# MCU_adacus_sch.net
KiCad netlist of a schematic drawn in Altium Designer
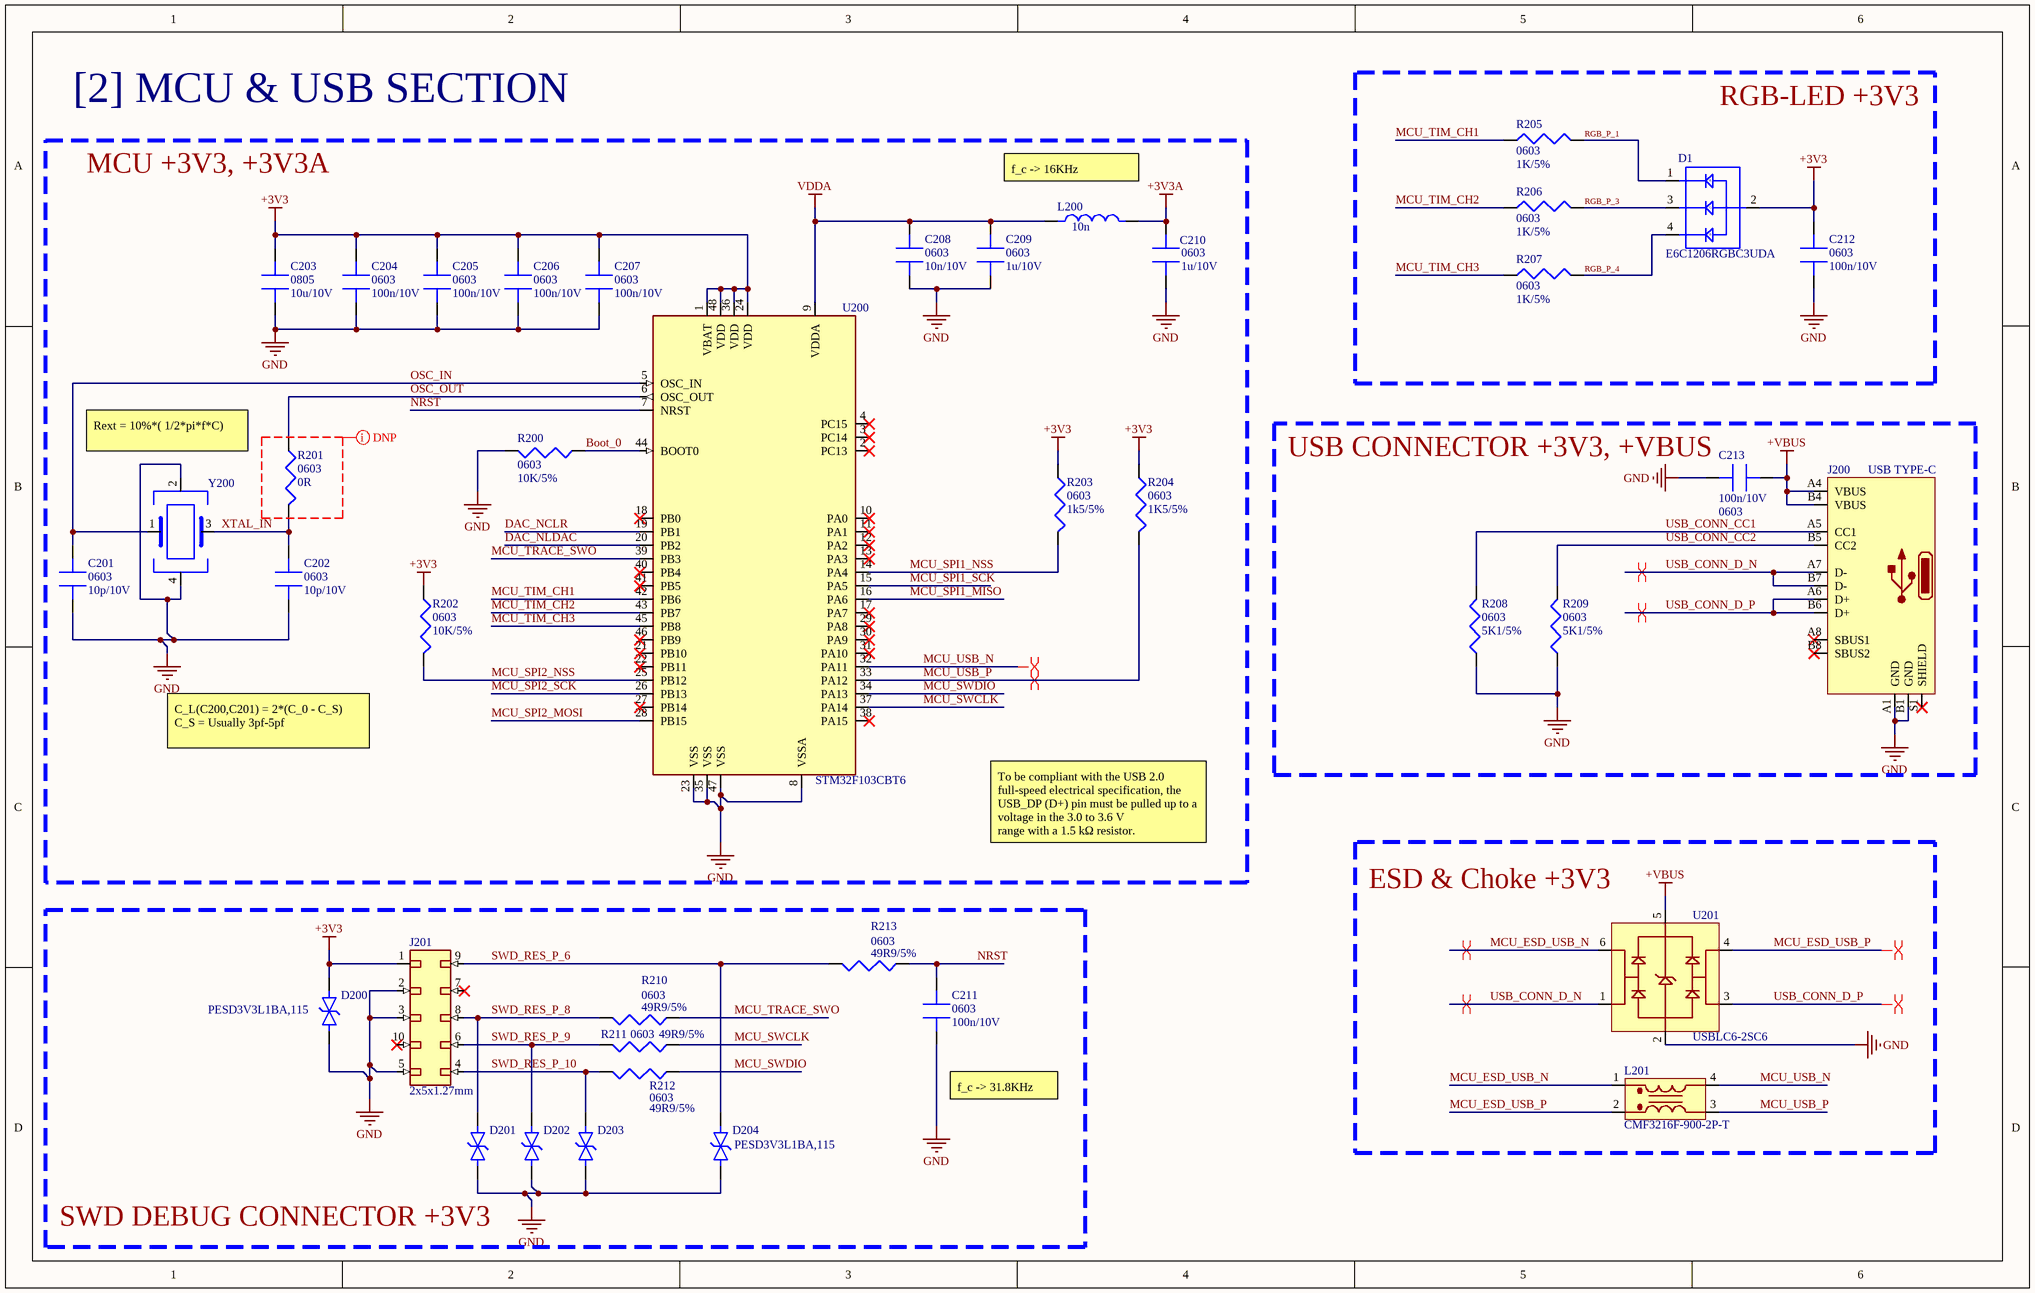
[diagram p0: MCU_adacus_sch.SchDoc]

(export (version "E")
  (design (tool "Eeschema 10.0.6"))
  (components
    (comp (ref "C201")
      (value "10p/10V")
      (footprint "[0603] CAPC1608X10M [A-LD]")
      (description "Standard Capacitor")
      (fields (field (name "PACKAGE") "0603") (field (name "Comment") "Capacitor"))
      (libsource (lib "adacus_schlib") (part "Capacitor"))
    )
    (comp (ref "C202")
      (value "10p/10V")
      (footprint "[0603] CAPC1608X10M [A-LD]")
      (description "Standard Capacitor")
      (fields (field (name "PACKAGE") "0603") (field (name "Comment") "Capacitor"))
      (libsource (lib "adacus_schlib") (part "Capacitor"))
    )
    (comp (ref "C203")
      (value "10u/10V")
      (footprint "[0805] CAPC2012X09M [A - LD]")
      (description "Standard Capacitor")
      (fields (field (name "PACKAGE") "0805") (field (name "Comment") "Capacitor"))
      (libsource (lib "adacus_schlib") (part "Capacitor"))
    )
    (comp (ref "C204")
      (value "100n/10V")
      (footprint "[0603] CAPC1608X10M [A-LD]")
      (description "Standard Capacitor")
      (fields (field (name "PACKAGE") "0603") (field (name "Comment") "Capacitor"))
      (libsource (lib "adacus_schlib") (part "Capacitor"))
    )
    (comp (ref "C205")
      (value "100n/10V")
      (footprint "[0603] CAPC1608X10M [A-LD]")
      (description "Standard Capacitor")
      (fields (field (name "PACKAGE") "0603") (field (name "Comment") "Capacitor"))
      (libsource (lib "adacus_schlib") (part "Capacitor"))
    )
    (comp (ref "C206")
      (value "100n/10V")
      (footprint "[0603] CAPC1608X10M [A-LD]")
      (description "Standard Capacitor")
      (fields (field (name "PACKAGE") "0603") (field (name "Comment") "Capacitor"))
      (libsource (lib "adacus_schlib") (part "Capacitor"))
    )
    (comp (ref "C207")
      (value "100n/10V")
      (footprint "[0603] CAPC1608X10M [A-LD]")
      (description "Standard Capacitor")
      (fields (field (name "PACKAGE") "0603") (field (name "Comment") "Capacitor"))
      (libsource (lib "adacus_schlib") (part "Capacitor"))
    )
    (comp (ref "C208")
      (value "10n/10V")
      (footprint "[0603] CAPC1608X10M [A-LD]")
      (description "Standard Capacitor")
      (fields (field (name "PACKAGE") "0603") (field (name "Comment") "Capacitor"))
      (libsource (lib "adacus_schlib") (part "Capacitor"))
    )
    (comp (ref "C209")
      (value "1u/10V")
      (footprint "[0805] CAPC2012X09M [A - LD]")
      (description "Standard Capacitor")
      (fields (field (name "PACKAGE") "0603") (field (name "Comment") "Capacitor"))
      (libsource (lib "adacus_schlib") (part "Capacitor"))
    )
    (comp (ref "C210")
      (value "1u/10V")
      (footprint "[0805] CAPC2012X09M [A - LD]")
      (description "Standard Capacitor")
      (fields (field (name "PACKAGE") "0603") (field (name "Comment") "Capacitor"))
      (libsource (lib "adacus_schlib") (part "Capacitor"))
    )
    (comp (ref "C211")
      (value "100n/10V")
      (footprint "[0603] CAPC1608X10M [A-LD]")
      (description "Standard Capacitor")
      (fields (field (name "PACKAGE") "0603") (field (name "Comment") "Capacitor"))
      (libsource (lib "adacus_schlib") (part "Capacitor"))
    )
    (comp (ref "C212")
      (value "100n/10V")
      (footprint "[0603] CAPC1608X10M [A-LD]")
      (description "Standard Capacitor")
      (fields (field (name "PACKAGE") "0603") (field (name "Comment") "Capacitor"))
      (libsource (lib "adacus_schlib") (part "Capacitor"))
    )
    (comp (ref "C213")
      (value "100n/10V")
      (footprint "[0603] CAPC1608X10M [A-LD]")
      (description "Standard Capacitor")
      (fields (field (name "PACKAGE") "0603") (field (name "Comment") "Capacitor"))
      (libsource (lib "adacus_schlib") (part "Capacitor"))
    )
    (comp (ref "D1")
      (value "E6C1206RGBC3UDA")
      (footprint "E6C1206RGBC3UDA")
      (description "RGB 1206 Light Emitting Diodes (LED) ROHS")
      (libsource (lib "adacus_schlib") (part "LED_RGB"))
    )
    (comp (ref "D200")
      (value "PESD3V3L1BA,115")
      (footprint "SODFL250X110-2M")
      (description "ESD Suppressors / TVS Diodes PESD3V3L1BA/SOD323/SOD2")
      (libsource (lib "adacus_schlib") (part "PESD3V3L1BA,115"))
    )
    (comp (ref "D201")
      (value "PESD3V3L1BA,115")
      (footprint "SODFL250X110-2M")
      (description "ESD Suppressors / TVS Diodes PESD3V3L1BA/SOD323/SOD2")
      (libsource (lib "adacus_schlib") (part "PESD3V3L1BA,115"))
    )
    (comp (ref "D202")
      (value "PESD3V3L1BA,115")
      (footprint "SODFL250X110-2M")
      (description "ESD Suppressors / TVS Diodes PESD3V3L1BA/SOD323/SOD2")
      (libsource (lib "adacus_schlib") (part "PESD3V3L1BA,115"))
    )
    (comp (ref "D203")
      (value "PESD3V3L1BA,115")
      (footprint "SODFL250X110-2M")
      (description "ESD Suppressors / TVS Diodes PESD3V3L1BA/SOD323/SOD2")
      (libsource (lib "adacus_schlib") (part "PESD3V3L1BA,115"))
    )
    (comp (ref "D204")
      (value "PESD3V3L1BA,115")
      (footprint "SODFL250X110-2M")
      (description "ESD Suppressors / TVS Diodes PESD3V3L1BA/SOD323/SOD2")
      (libsource (lib "adacus_schlib") (part "PESD3V3L1BA,115"))
    )
    (comp (ref "J200")
      (value "USB TYPE-C")
      (footprint "HRO_TYPE-C-31-M-12")
      (libsource (lib "adacus_schlib") (part "USB TYPE-C"))
    )
    (comp (ref "J201")
      (value "2x5x1.27mm")
      (footprint "2X10_BOXHEADER")
      (description "SWD Connector 2x5x1.27mm pin count")
      (libsource (lib "adacus_schlib") (part "SWD Connector"))
    )
    (comp (ref "L200")
      (value "10n")
      (footprint "PM0603-10NJ")
      (description "Standard Inductor")
      (fields (field (name "Comment") "Inductor"))
      (libsource (lib "adacus_schlib") (part "Inductor"))
    )
    (comp (ref "L201")
      (value "CMF3216F-900-2P-T")
      (footprint "CMF3216F-900-2P-T")
      (description "90Ω@100MHz 0.3Ω 2 1206 Common Mode Filters ROHS")
      (libsource (lib "adacus_schlib") (part "CMF3216F-900-2P-T"))
    )
    (comp (ref "R200")
      (value "10K/5%")
      (footprint "[0603] RESC1608X06M [A-LD]")
      (description "Standard Resistor")
      (fields (field (name "PACKAGE") "0603") (field (name "Comment") "Resistor"))
      (libsource (lib "adacus_schlib") (part "Resistor"))
    )
    (comp (ref "R201")
      (value "0R")
      (footprint "[0603] RESC1608X06M [A-LD]")
      (description "Standard Resistor")
      (fields (field (name "PACKAGE") "0603") (field (name "Comment") "Resistor"))
      (libsource (lib "adacus_schlib") (part "Resistor"))
    )
    (comp (ref "R202")
      (value "10K/5%")
      (footprint "[0603] RESC1608X06M [A-LD]")
      (description "Standard Resistor")
      (fields (field (name "PACKAGE") "0603") (field (name "Comment") "Resistor"))
      (libsource (lib "adacus_schlib") (part "Resistor"))
    )
    (comp (ref "R203")
      (value "1k5/5%")
      (footprint "[0603] RESC1608X06M [A-LD]")
      (description "Standard Resistor")
      (fields (field (name "PACKAGE") "0603") (field (name "Comment") "Resistor"))
      (libsource (lib "adacus_schlib") (part "Resistor"))
    )
    (comp (ref "R204")
      (value "1K5/5%")
      (footprint "[0603] RESC1608X06M [A-LD]")
      (description "Standard Resistor")
      (fields (field (name "PACKAGE") "0603") (field (name "Comment") "Resistor"))
      (libsource (lib "adacus_schlib") (part "Resistor"))
    )
    (comp (ref "R205")
      (value "1K/5%")
      (footprint "[0603] RESC1608X06M [A-LD]")
      (description "Standard Resistor")
      (fields (field (name "PACKAGE") "0603") (field (name "Comment") "Resistor"))
      (libsource (lib "adacus_schlib") (part "Resistor"))
    )
    (comp (ref "R206")
      (value "1K/5%")
      (footprint "[0603] RESC1608X06M [A-LD]")
      (description "Standard Resistor")
      (fields (field (name "PACKAGE") "0603") (field (name "Comment") "Resistor"))
      (libsource (lib "adacus_schlib") (part "Resistor"))
    )
    (comp (ref "R207")
      (value "1K/5%")
      (footprint "[0603] RESC1608X06M [A-LD]")
      (description "Standard Resistor")
      (fields (field (name "PACKAGE") "0603") (field (name "Comment") "Resistor"))
      (libsource (lib "adacus_schlib") (part "Resistor"))
    )
    (comp (ref "R208")
      (value "5K1/5%")
      (footprint "[0603] RESC1608X06M [A-LD]")
      (description "Standard Resistor")
      (fields (field (name "PACKAGE") "0603") (field (name "Comment") "Resistor"))
      (libsource (lib "adacus_schlib") (part "Resistor"))
    )
    (comp (ref "R209")
      (value "5K1/5%")
      (footprint "[0603] RESC1608X06M [A-LD]")
      (description "Standard Resistor")
      (fields (field (name "PACKAGE") "0603") (field (name "Comment") "Resistor"))
      (libsource (lib "adacus_schlib") (part "Resistor"))
    )
    (comp (ref "R210")
      (value "49R9/5%")
      (footprint "[0603] RESC1608X06M [A-LD]")
      (description "Standard Resistor")
      (fields (field (name "PACKAGE") "0603") (field (name "Comment") "Resistor"))
      (libsource (lib "adacus_schlib") (part "Resistor"))
    )
    (comp (ref "R211")
      (value "49R9/5%")
      (footprint "[0603] RESC1608X06M [A-LD]")
      (description "Standard Resistor")
      (fields (field (name "PACKAGE") "0603") (field (name "Comment") "Resistor"))
      (libsource (lib "adacus_schlib") (part "Resistor"))
    )
    (comp (ref "R212")
      (value "49R9/5%")
      (footprint "[0603] RESC1608X06M [A-LD]")
      (description "Standard Resistor")
      (fields (field (name "PACKAGE") "0603") (field (name "Comment") "Resistor"))
      (libsource (lib "adacus_schlib") (part "Resistor"))
    )
    (comp (ref "R213")
      (value "49R9/5%")
      (footprint "[0603] RESC1608X06M [A-LD]")
      (description "Standard Resistor")
      (fields (field (name "PACKAGE") "0603") (field (name "Comment") "Resistor"))
      (libsource (lib "adacus_schlib") (part "Resistor"))
    )
    (comp (ref "U200")
      (value "STM32F103CBT6")
      (footprint "TSQFP50P900X900X160-48M")
      (description "ARM Microcontrollers - MCU 32BIT Cortex M3 128K MED Performance LN")
      (libsource (lib "adacus_schlib") (part "STM32F103CBT6"))
    )
    (comp (ref "U201")
      (value "USBLC6-2SC6")
      (footprint "SOT95P280X145-6M")
      (description "Very low capacitance ESD protection")
      (libsource (lib "adacus_schlib") (part "USBLC6-2"))
    )
    (comp (ref "Y200")
      (value "ECS-2016MV-160-DN")
      (footprint "ECS-2016MV-160-DN")
      (libsource (lib "adacus_schlib") (part "ECS-2016MV-160-DN"))
    )
  )
  (nets
    (net (code "1") (name "+3V3") (class "Default")
      (node (ref "C203") (pin "2") (pinfunction "2_2") (pintype "passive"))
      (node (ref "C204") (pin "2") (pinfunction "2_2") (pintype "passive"))
      (node (ref "C205") (pin "2") (pinfunction "2_2") (pintype "passive"))
      (node (ref "C206") (pin "2") (pinfunction "2_2") (pintype "passive"))
      (node (ref "C207") (pin "2") (pinfunction "2_2") (pintype "passive"))
      (node (ref "C212") (pin "2") (pinfunction "2_2") (pintype "passive"))
      (node (ref "D1") (pin "2") (pinfunction "2_2") (pintype "passive"))
      (node (ref "D200") (pin "2") (pinfunction "2_2") (pintype "passive"))
      (node (ref "J201") (pin "1") (pinfunction "VCC_1") (pintype "power_in"))
      (node (ref "R202") (pin "2") (pinfunction "2_2") (pintype "passive"))
      (node (ref "R203") (pin "2") (pinfunction "2_2") (pintype "passive"))
      (node (ref "R204") (pin "2") (pinfunction "2_2") (pintype "passive"))
      (node (ref "U200") (pin "1") (pinfunction "VBAT_1") (pintype "power_in"))
      (node (ref "U200") (pin "24") (pinfunction "VDD_24") (pintype "power_in"))
      (node (ref "U200") (pin "36") (pinfunction "VDD_36") (pintype "power_in"))
      (node (ref "U200") (pin "48") (pinfunction "VDD_48") (pintype "power_in"))
    )
    (net (code "2") (name "+3V3A") (class "Default")
      (node (ref "C210") (pin "2") (pinfunction "2_2") (pintype "passive"))
      (node (ref "L200") (pin "1") (pinfunction "1_1") (pintype "passive"))
    )
    (net (code "3") (name "+VBUS") (class "Default")
      (node (ref "C213") (pin "2") (pinfunction "2_2") (pintype "passive"))
      (node (ref "J200") (pin "A4") (pinfunction "VBUS_A4") (pintype "passive"))
      (node (ref "J200") (pin "B4") (pinfunction "VBUS_B4") (pintype "passive"))
      (node (ref "U201") (pin "5") (pinfunction "5_5") (pintype "passive"))
    )
    (net (code "4") (name "/Boot_0") (class "Default")
      (node (ref "R200") (pin "2") (pinfunction "2_2") (pintype "passive"))
      (node (ref "U200") (pin "44") (pinfunction "BOOT0_44") (pintype "input"))
    )
    (net (code "5") (name "/DAC_NCLR") (class "Default")
      (node (ref "U200") (pin "19") (pinfunction "PB1_19") (pintype "bidirectional"))
    )
    (net (code "6") (name "/DAC_NLDAC") (class "Default")
      (node (ref "U200") (pin "20") (pinfunction "PB2_20") (pintype "bidirectional"))
    )
    (net (code "7") (name "/MCU_ESD_USB_N") (class "Default")
      (node (ref "L201") (pin "1") (pinfunction "1_1") (pintype "passive"))
      (node (ref "U201") (pin "6") (pinfunction "6_6") (pintype "passive"))
    )
    (net (code "8") (name "/MCU_ESD_USB_P") (class "Default")
      (node (ref "L201") (pin "2") (pinfunction "2_2") (pintype "passive"))
      (node (ref "U201") (pin "4") (pinfunction "4_4") (pintype "passive"))
    )
    (net (code "9") (name "/MCU_SPI1_MISO") (class "Default")
      (node (ref "U200") (pin "16") (pinfunction "PA6_16") (pintype "bidirectional"))
    )
    (net (code "10") (name "/MCU_SPI1_NSS") (class "Default")
      (node (ref "R203") (pin "1") (pinfunction "1_1") (pintype "passive"))
      (node (ref "U200") (pin "14") (pinfunction "PA4_14") (pintype "bidirectional"))
    )
    (net (code "11") (name "/MCU_SPI1_SCK") (class "Default")
      (node (ref "U200") (pin "15") (pinfunction "PA5_15") (pintype "bidirectional"))
    )
    (net (code "12") (name "/MCU_SPI2_MOSI") (class "Default")
      (node (ref "U200") (pin "28") (pinfunction "PB15_28") (pintype "bidirectional"))
    )
    (net (code "13") (name "/MCU_SPI2_NSS") (class "Default")
      (node (ref "R202") (pin "1") (pinfunction "1_1") (pintype "passive"))
      (node (ref "U200") (pin "25") (pinfunction "PB12_25") (pintype "bidirectional"))
    )
    (net (code "14") (name "/MCU_SPI2_SCK") (class "Default")
      (node (ref "U200") (pin "26") (pinfunction "PB13_26") (pintype "bidirectional"))
    )
    (net (code "15") (name "/MCU_SWCLK") (class "Default")
      (node (ref "R211") (pin "2") (pinfunction "2_2") (pintype "passive"))
      (node (ref "U200") (pin "37") (pinfunction "PA14_37") (pintype "bidirectional"))
    )
    (net (code "16") (name "/MCU_SWDIO") (class "Default")
      (node (ref "R212") (pin "2") (pinfunction "2_2") (pintype "passive"))
      (node (ref "U200") (pin "34") (pinfunction "PA13_34") (pintype "bidirectional"))
    )
    (net (code "17") (name "/MCU_TIM_CH1") (class "Default")
      (node (ref "R205") (pin "2") (pinfunction "2_2") (pintype "passive"))
      (node (ref "U200") (pin "42") (pinfunction "PB6_42") (pintype "bidirectional"))
    )
    (net (code "18") (name "/MCU_TIM_CH2") (class "Default")
      (node (ref "R206") (pin "2") (pinfunction "2_2") (pintype "passive"))
      (node (ref "U200") (pin "43") (pinfunction "PB7_43") (pintype "bidirectional"))
    )
    (net (code "19") (name "/MCU_TIM_CH3") (class "Default")
      (node (ref "R207") (pin "2") (pinfunction "2_2") (pintype "passive"))
      (node (ref "U200") (pin "45") (pinfunction "PB8_45") (pintype "bidirectional"))
    )
    (net (code "20") (name "/MCU_TRACE_SWO") (class "Default")
      (node (ref "R210") (pin "2") (pinfunction "2_2") (pintype "passive"))
      (node (ref "U200") (pin "39") (pinfunction "PB3_39") (pintype "bidirectional"))
    )
    (net (code "21") (name "/MCU_USB_N") (class "Default")
      (node (ref "L201") (pin "4") (pinfunction "4_4") (pintype "passive"))
      (node (ref "U200") (pin "32") (pinfunction "PA11_32") (pintype "bidirectional"))
    )
    (net (code "22") (name "/MCU_USB_P") (class "Default")
      (node (ref "L201") (pin "3") (pinfunction "3_3") (pintype "passive"))
      (node (ref "R204") (pin "1") (pinfunction "1_1") (pintype "passive"))
      (node (ref "U200") (pin "33") (pinfunction "PA12_33") (pintype "bidirectional"))
    )
    (net (code "23") (name "/NRST") (class "Default")
      (node (ref "C211") (pin "2") (pinfunction "2_2") (pintype "passive"))
      (node (ref "R213") (pin "2") (pinfunction "2_2") (pintype "passive"))
      (node (ref "U200") (pin "7") (pinfunction "NRST_7") (pintype "bidirectional"))
    )
    (net (code "24") (name "/OSC_IN") (class "Default")
      (node (ref "C201") (pin "2") (pinfunction "2_2") (pintype "passive"))
      (node (ref "U200") (pin "5") (pinfunction "OSC_IN_5") (pintype "input"))
      (node (ref "Y200") (pin "1") (pinfunction "1_1") (pintype "passive"))
    )
    (net (code "25") (name "/OSC_OUT") (class "Default")
      (node (ref "R201") (pin "2") (pinfunction "2_2") (pintype "passive"))
      (node (ref "U200") (pin "6") (pinfunction "OSC_OUT_6") (pintype "output"))
    )
    (net (code "26") (name "/RGB_P_1") (class "Default")
      (node (ref "D1") (pin "1") (pinfunction "1_1") (pintype "passive"))
      (node (ref "R205") (pin "1") (pinfunction "1_1") (pintype "passive"))
    )
    (net (code "27") (name "/RGB_P_3") (class "Default")
      (node (ref "D1") (pin "3") (pinfunction "3_3") (pintype "passive"))
      (node (ref "R206") (pin "1") (pinfunction "1_1") (pintype "passive"))
    )
    (net (code "28") (name "/RGB_P_4") (class "Default")
      (node (ref "D1") (pin "4") (pinfunction "4_4") (pintype "passive"))
      (node (ref "R207") (pin "1") (pinfunction "1_1") (pintype "passive"))
    )
    (net (code "29") (name "/SWD_RES_P_6") (class "Default")
      (node (ref "D204") (pin "2") (pinfunction "2_2") (pintype "passive"))
      (node (ref "J201") (pin "9") (pinfunction "TDO_9") (pintype "input"))
      (node (ref "R213") (pin "1") (pinfunction "1_1") (pintype "passive"))
    )
    (net (code "30") (name "/SWD_RES_P_8") (class "Default")
      (node (ref "D201") (pin "2") (pinfunction "2_2") (pintype "passive"))
      (node (ref "J201") (pin "8") (pinfunction "TDI_8") (pintype "input"))
      (node (ref "R210") (pin "1") (pinfunction "1_1") (pintype "passive"))
    )
    (net (code "31") (name "/SWD_RES_P_9") (class "Default")
      (node (ref "D202") (pin "2") (pinfunction "2_2") (pintype "passive"))
      (node (ref "J201") (pin "6") (pinfunction "TCK_6") (pintype "input"))
      (node (ref "R211") (pin "1") (pinfunction "1_1") (pintype "passive"))
    )
    (net (code "32") (name "/SWD_RES_P_10") (class "Default")
      (node (ref "D203") (pin "2") (pinfunction "2_2") (pintype "passive"))
      (node (ref "J201") (pin "4") (pinfunction "nRESET_4") (pintype "input"))
      (node (ref "R212") (pin "1") (pinfunction "1_1") (pintype "passive"))
    )
    (net (code "33") (name "/USB_CONN_CC1") (class "Default")
      (node (ref "J200") (pin "A5") (pinfunction "CC1_A5") (pintype "passive"))
      (node (ref "R208") (pin "1") (pinfunction "1_1") (pintype "passive"))
    )
    (net (code "34") (name "/USB_CONN_CC2") (class "Default")
      (node (ref "J200") (pin "B5") (pinfunction "CC2_B5") (pintype "passive"))
      (node (ref "R209") (pin "1") (pinfunction "1_1") (pintype "passive"))
    )
    (net (code "35") (name "/USB_CONN_D_N") (class "Default")
      (node (ref "J200") (pin "A7") (pinfunction "D-_A7") (pintype "passive"))
      (node (ref "J200") (pin "B7") (pinfunction "D-_B7") (pintype "passive"))
      (node (ref "U201") (pin "1") (pinfunction "1_1") (pintype "passive"))
    )
    (net (code "36") (name "/USB_CONN_D_P") (class "Default")
      (node (ref "J200") (pin "A6") (pinfunction "D+_A6") (pintype "passive"))
      (node (ref "J200") (pin "B6") (pinfunction "D+_B6") (pintype "passive"))
      (node (ref "U201") (pin "3") (pinfunction "3_3") (pintype "passive"))
    )
    (net (code "37") (name "/XTAL_IN") (class "Default")
      (node (ref "C202") (pin "2") (pinfunction "2_2") (pintype "passive"))
      (node (ref "R201") (pin "1") (pinfunction "1_1") (pintype "passive"))
      (node (ref "Y200") (pin "3") (pinfunction "3_3") (pintype "passive"))
    )
    (net (code "38") (name "GND") (class "Default")
      (node (ref "C201") (pin "1") (pinfunction "1_1") (pintype "passive"))
      (node (ref "C202") (pin "1") (pinfunction "1_1") (pintype "passive"))
      (node (ref "C203") (pin "1") (pinfunction "1_1") (pintype "passive"))
      (node (ref "C204") (pin "1") (pinfunction "1_1") (pintype "passive"))
      (node (ref "C205") (pin "1") (pinfunction "1_1") (pintype "passive"))
      (node (ref "C206") (pin "1") (pinfunction "1_1") (pintype "passive"))
      (node (ref "C207") (pin "1") (pinfunction "1_1") (pintype "passive"))
      (node (ref "C208") (pin "1") (pinfunction "1_1") (pintype "passive"))
      (node (ref "C209") (pin "1") (pinfunction "1_1") (pintype "passive"))
      (node (ref "C210") (pin "1") (pinfunction "1_1") (pintype "passive"))
      (node (ref "C211") (pin "1") (pinfunction "1_1") (pintype "passive"))
      (node (ref "C212") (pin "1") (pinfunction "1_1") (pintype "passive"))
      (node (ref "C213") (pin "1") (pinfunction "1_1") (pintype "passive"))
      (node (ref "D200") (pin "1") (pinfunction "1_1") (pintype "passive"))
      (node (ref "D201") (pin "1") (pinfunction "1_1") (pintype "passive"))
      (node (ref "D202") (pin "1") (pinfunction "1_1") (pintype "passive"))
      (node (ref "D203") (pin "1") (pinfunction "1_1") (pintype "passive"))
      (node (ref "D204") (pin "1") (pinfunction "1_1") (pintype "passive"))
      (node (ref "J200") (pin "A1") (pinfunction "GND_A1") (pintype "passive"))
      (node (ref "J200") (pin "B1") (pinfunction "GND_B1") (pintype "passive"))
      (node (ref "J201") (pin "2") (pinfunction "TMS_2") (pintype "input"))
      (node (ref "J201") (pin "3") (pinfunction "GND_3") (pintype "input"))
      (node (ref "J201") (pin "5") (pinfunction "GND_5") (pintype "input"))
      (node (ref "R200") (pin "1") (pinfunction "1_1") (pintype "passive"))
      (node (ref "R208") (pin "2") (pinfunction "2_2") (pintype "passive"))
      (node (ref "R209") (pin "2") (pinfunction "2_2") (pintype "passive"))
      (node (ref "U200") (pin "23") (pinfunction "VSS_23") (pintype "power_in"))
      (node (ref "U200") (pin "35") (pinfunction "VSS_35") (pintype "power_in"))
      (node (ref "U200") (pin "47") (pinfunction "VSS_47") (pintype "power_in"))
      (node (ref "U200") (pin "8") (pinfunction "VSSA_8") (pintype "power_in"))
      (node (ref "U201") (pin "2") (pinfunction "2_2") (pintype "passive"))
      (node (ref "Y200") (pin "2") (pinfunction "3_2") (pintype "passive"))
      (node (ref "Y200") (pin "4") (pinfunction "4_4") (pintype "passive"))
    )
    (net (code "39") (name "VDDA") (class "Default")
      (node (ref "C208") (pin "2") (pinfunction "2_2") (pintype "passive"))
      (node (ref "C209") (pin "2") (pinfunction "2_2") (pintype "passive"))
      (node (ref "L200") (pin "2") (pinfunction "2_2") (pintype "passive"))
      (node (ref "U200") (pin "9") (pinfunction "VDDA_9") (pintype "power_in"))
    )
    (net (code "40") (name "unconnected-(J200-SBUS1-PadA8)") (class "Default")
      (node (ref "J200") (pin "A8") (pinfunction "SBUS1_A8") (pintype "passive+no_connect"))
    )
    (net (code "41") (name "unconnected-(J200-SBUS2-PadB8)") (class "Default")
      (node (ref "J200") (pin "B8") (pinfunction "SBUS2_B8") (pintype "passive+no_connect"))
    )
    (net (code "42") (name "unconnected-(J200-SHIELD-PadS1)") (class "Default")
      (node (ref "J200") (pin "S1") (pinfunction "SHIELD_S1") (pintype "passive+no_connect"))
    )
    (net (code "43") (name "unconnected-(J201-GND-Pad10)") (class "Default")
      (node (ref "J201") (pin "10") (pinfunction "GND_10") (pintype "input+no_connect"))
    )
    (net (code "44") (name "unconnected-(J201-KEY-Pad7)") (class "Default")
      (node (ref "J201") (pin "7") (pinfunction "KEY_7") (pintype "input+no_connect"))
    )
    (net (code "45") (name "unconnected-(U200-PA0-Pad10)") (class "Default")
      (node (ref "U200") (pin "10") (pinfunction "PA0_10") (pintype "bidirectional+no_connect"))
    )
    (net (code "46") (name "unconnected-(U200-PA1-Pad11)") (class "Default")
      (node (ref "U200") (pin "11") (pinfunction "PA1_11") (pintype "bidirectional+no_connect"))
    )
    (net (code "47") (name "unconnected-(U200-PA2-Pad12)") (class "Default")
      (node (ref "U200") (pin "12") (pinfunction "PA2_12") (pintype "bidirectional+no_connect"))
    )
    (net (code "48") (name "unconnected-(U200-PA3-Pad13)") (class "Default")
      (node (ref "U200") (pin "13") (pinfunction "PA3_13") (pintype "bidirectional+no_connect"))
    )
    (net (code "49") (name "unconnected-(U200-PA7-Pad17)") (class "Default")
      (node (ref "U200") (pin "17") (pinfunction "PA7_17") (pintype "bidirectional+no_connect"))
    )
    (net (code "50") (name "unconnected-(U200-PA8-Pad29)") (class "Default")
      (node (ref "U200") (pin "29") (pinfunction "PA8_29") (pintype "bidirectional+no_connect"))
    )
    (net (code "51") (name "unconnected-(U200-PA9-Pad30)") (class "Default")
      (node (ref "U200") (pin "30") (pinfunction "PA9_30") (pintype "bidirectional+no_connect"))
    )
    (net (code "52") (name "unconnected-(U200-PA10-Pad31)") (class "Default")
      (node (ref "U200") (pin "31") (pinfunction "PA10_31") (pintype "bidirectional+no_connect"))
    )
    (net (code "53") (name "unconnected-(U200-PA15-Pad38)") (class "Default")
      (node (ref "U200") (pin "38") (pinfunction "PA15_38") (pintype "bidirectional+no_connect"))
    )
    (net (code "54") (name "unconnected-(U200-PB0-Pad18)") (class "Default")
      (node (ref "U200") (pin "18") (pinfunction "PB0_18") (pintype "bidirectional+no_connect"))
    )
    (net (code "55") (name "unconnected-(U200-PB4-Pad40)") (class "Default")
      (node (ref "U200") (pin "40") (pinfunction "PB4_40") (pintype "bidirectional+no_connect"))
    )
    (net (code "56") (name "unconnected-(U200-PB5-Pad41)") (class "Default")
      (node (ref "U200") (pin "41") (pinfunction "PB5_41") (pintype "bidirectional+no_connect"))
    )
    (net (code "57") (name "unconnected-(U200-PB9-Pad46)") (class "Default")
      (node (ref "U200") (pin "46") (pinfunction "PB9_46") (pintype "bidirectional+no_connect"))
    )
    (net (code "58") (name "unconnected-(U200-PB10-Pad21)") (class "Default")
      (node (ref "U200") (pin "21") (pinfunction "PB10_21") (pintype "bidirectional+no_connect"))
    )
    (net (code "59") (name "unconnected-(U200-PB11-Pad22)") (class "Default")
      (node (ref "U200") (pin "22") (pinfunction "PB11_22") (pintype "bidirectional+no_connect"))
    )
    (net (code "60") (name "unconnected-(U200-PB14-Pad27)") (class "Default")
      (node (ref "U200") (pin "27") (pinfunction "PB14_27") (pintype "bidirectional+no_connect"))
    )
    (net (code "61") (name "unconnected-(U200-PC13-Pad2)") (class "Default")
      (node (ref "U200") (pin "2") (pinfunction "PC13_2") (pintype "bidirectional+no_connect"))
    )
    (net (code "62") (name "unconnected-(U200-PC14-Pad3)") (class "Default")
      (node (ref "U200") (pin "3") (pinfunction "PC14_3") (pintype "bidirectional+no_connect"))
    )
    (net (code "63") (name "unconnected-(U200-PC15-Pad4)") (class "Default")
      (node (ref "U200") (pin "4") (pinfunction "PC15_4") (pintype "bidirectional+no_connect"))
    )
  )
)
